# Sheet2.net
KiCad netlist of a schematic drawn in Altium Designer
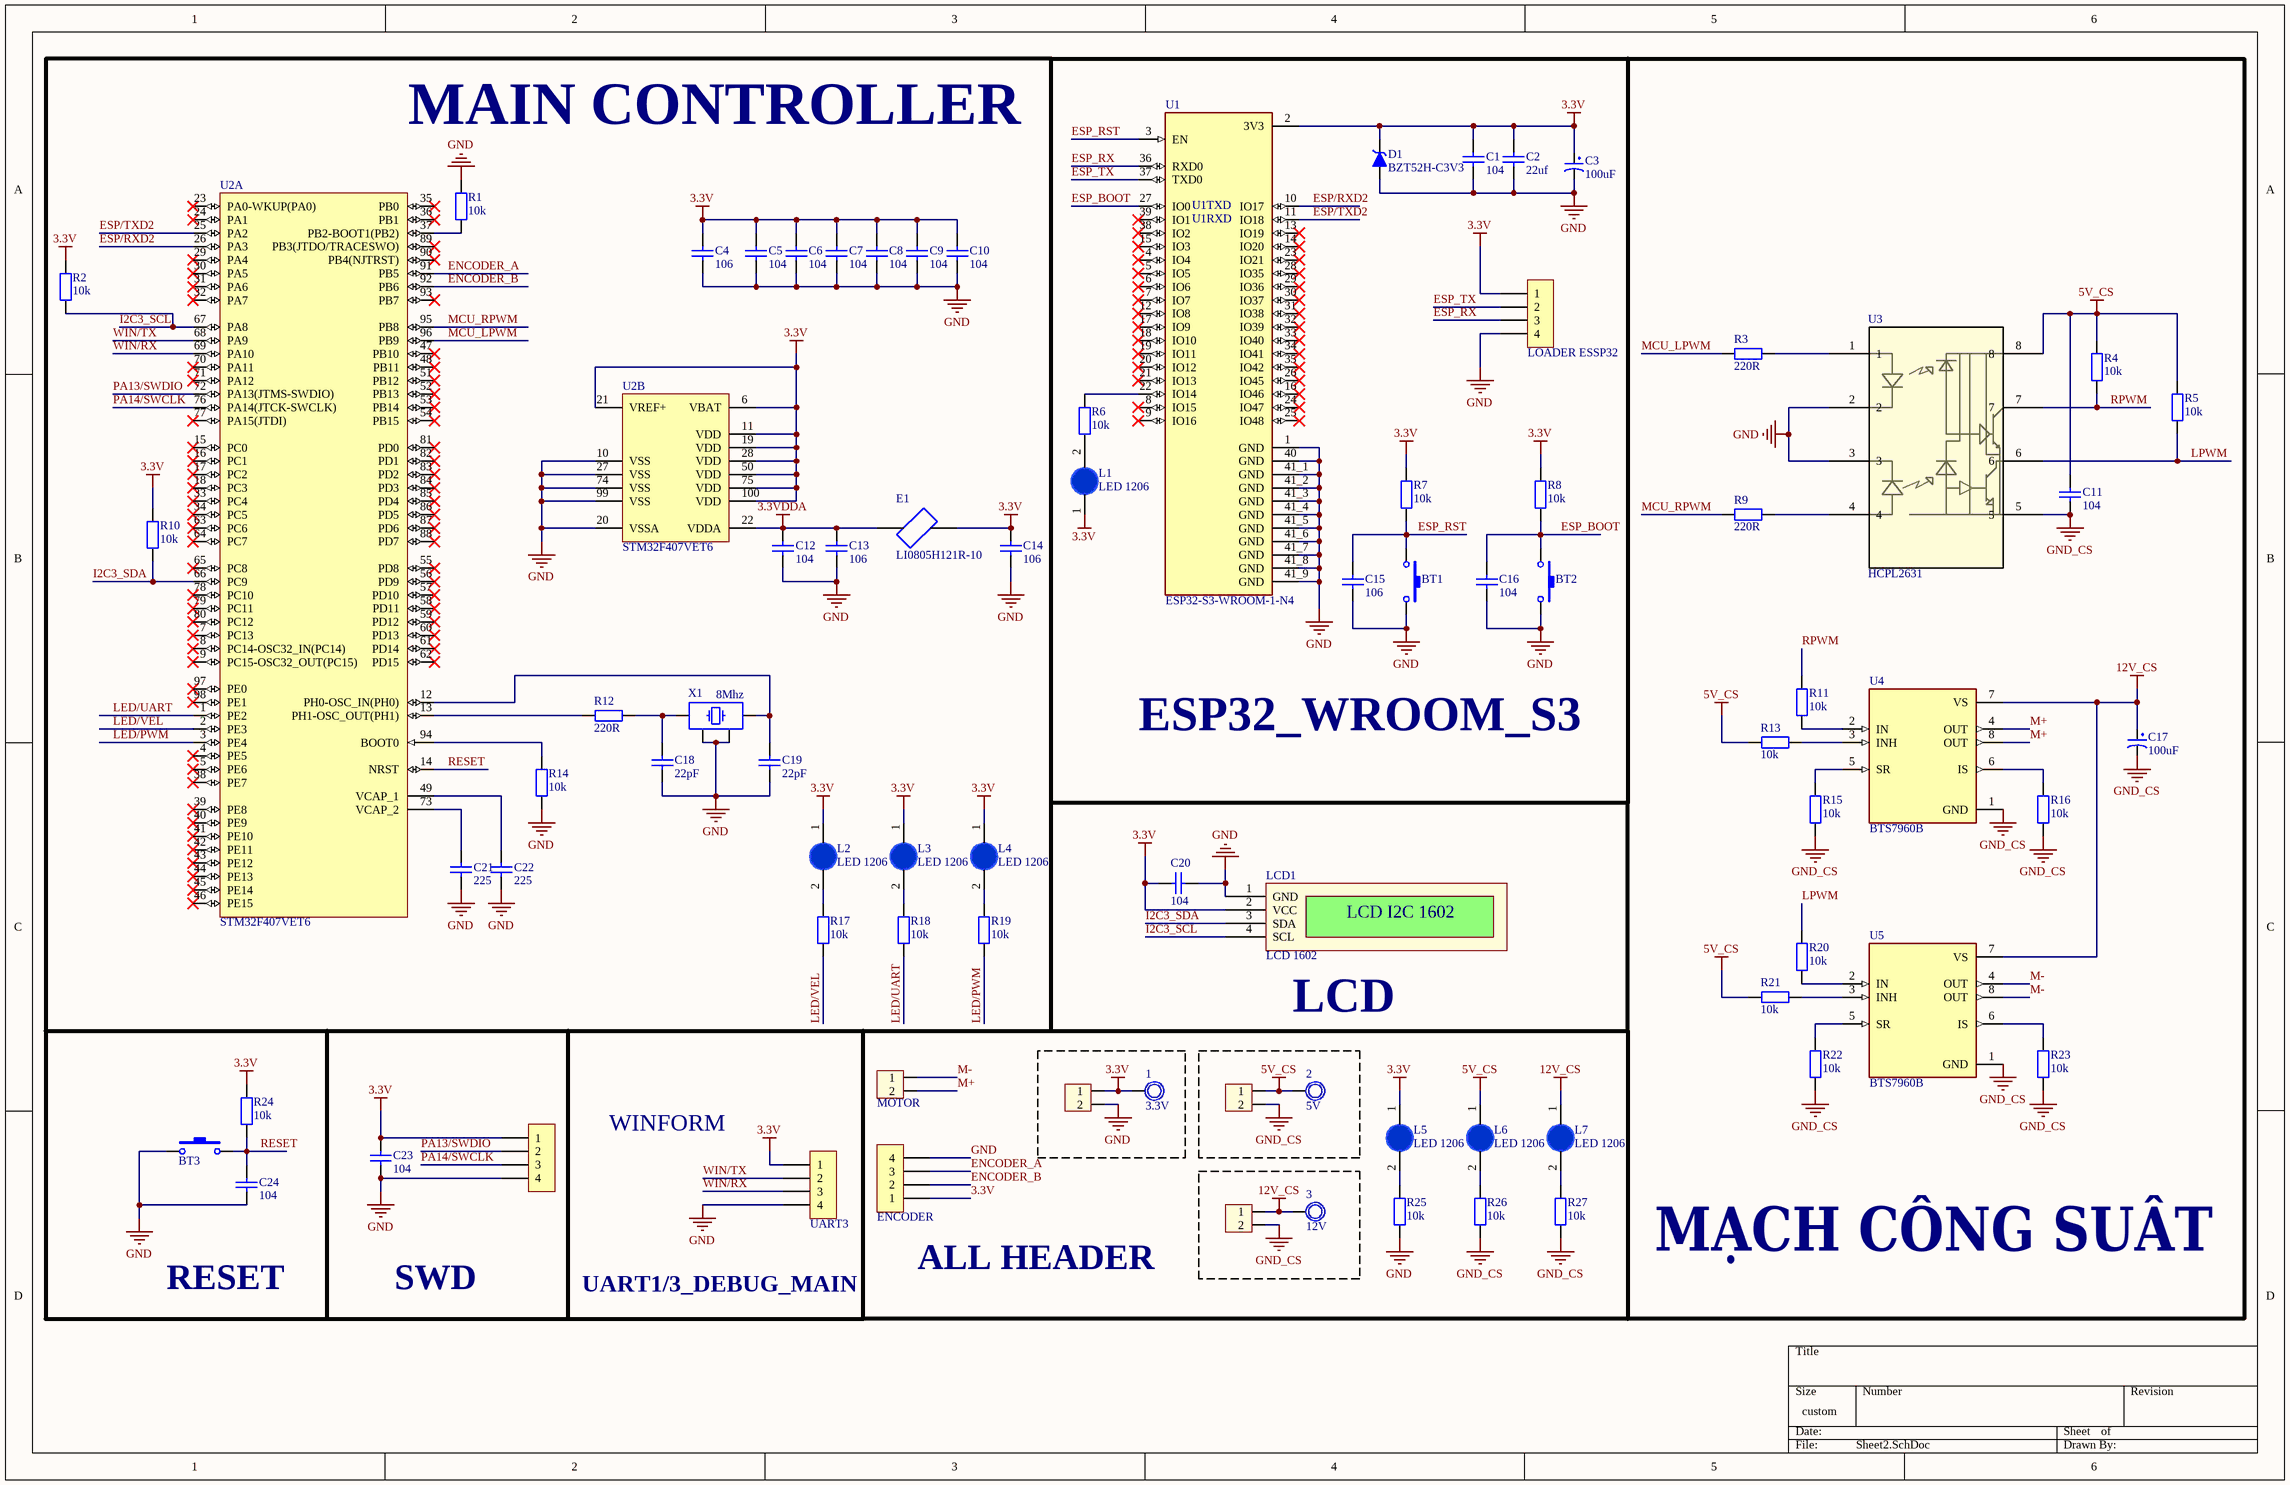
[diagram p0: Sheet2.SchDoc]

(export (version "E")
  (design (tool "Eeschema 10.0.6"))
  (components
    (comp (ref "1")
      (value "3.3V")
      (footprint "TP1")
      (description "Test Point")
      (libsource (lib "syhaunguyen") (part "TP1"))
    )
    (comp (ref "2")
      (value "5V")
      (footprint "TP1")
      (description "Test Point")
      (libsource (lib "syhaunguyen") (part "TP1"))
    )
    (comp (ref "3")
      (value "12V")
      (footprint "TP1")
      (description "Test Point")
      (libsource (lib "syhaunguyen") (part "TP1"))
    )
    (comp (ref "BT1")
      (value "Nut Nhan 2 Chan SMD 3x6x2.5")
      (footprint "Nut Nhan 2 Chan SMD 3x6x2.5")
      (libsource (lib "Altium_Lib_by_KhueNguyenCreator") (part "Nut Nhan 2 Chan SMD 3x6x2.5"))
    )
    (comp (ref "BT2")
      (value "Nut Nhan 2 Chan SMD 3x6x2.5")
      (footprint "Nut Nhan 2 Chan SMD 3x6x2.5")
      (libsource (lib "Altium_Lib_by_KhueNguyenCreator") (part "Nut Nhan 2 Chan SMD 3x6x2.5"))
    )
    (comp (ref "BT3")
      (value "Nut Nhan 2 Chan SMD 3x6x2.5")
      (footprint "Nut Nhan 2 Chan SMD 3x6x2.5")
      (libsource (lib "Altium_Lib_by_KhueNguyenCreator") (part "Nut Nhan 2 Chan SMD 3x6x2.5"))
    )
    (comp (ref "C1")
      (value "104")
      (footprint "tu 0805")
      (description "Dán")
      (libsource (lib "Altium_Lib_by_KhueNguyenCreator") (part "Tu 0805 104 50V 10%"))
    )
    (comp (ref "C2")
      (value "22uf")
      (footprint "tu 0805")
      (description "Dán")
      (libsource (lib "Altium_Lib_by_KhueNguyenCreator") (part "Tu 0805 222 50V 10%"))
    )
    (comp (ref "C3")
      (value "100uF")
      (footprint "tu tantalum smd7343")
      (description "Dán")
      (libsource (lib "Altium_Lib_by_KhueNguyenCreator") (part "Tu tantalum 100uF 50V SMD7343"))
    )
    (comp (ref "C4")
      (value "106")
      (footprint "tu 0805")
      (description "Dán")
      (libsource (lib "Altium_Lib_by_KhueNguyenCreator") (part "Tu 0805 106 16V 10%"))
    )
    (comp (ref "C5")
      (value "104")
      (footprint "tu 0805")
      (description "Dán")
      (libsource (lib "Altium_Lib_by_KhueNguyenCreator") (part "Tu 0805 104 50V 10%"))
    )
    (comp (ref "C6")
      (value "104")
      (footprint "tu 0805")
      (description "Dán")
      (libsource (lib "Altium_Lib_by_KhueNguyenCreator") (part "Tu 0805 104 50V 10%"))
    )
    (comp (ref "C7")
      (value "104")
      (footprint "tu 0805")
      (description "Dán")
      (libsource (lib "Altium_Lib_by_KhueNguyenCreator") (part "Tu 0805 104 50V 10%"))
    )
    (comp (ref "C8")
      (value "104")
      (footprint "tu 0805")
      (description "Dán")
      (libsource (lib "Altium_Lib_by_KhueNguyenCreator") (part "Tu 0805 104 50V 10%"))
    )
    (comp (ref "C9")
      (value "104")
      (footprint "tu 0805")
      (description "Dán")
      (libsource (lib "Altium_Lib_by_KhueNguyenCreator") (part "Tu 0805 104 50V 10%"))
    )
    (comp (ref "C10")
      (value "104")
      (footprint "tu 0805")
      (description "Dán")
      (libsource (lib "Altium_Lib_by_KhueNguyenCreator") (part "Tu 0805 104 50V 10%"))
    )
    (comp (ref "C11")
      (value "104")
      (footprint "tu 0805")
      (description "Dán")
      (libsource (lib "Altium_Lib_by_KhueNguyenCreator") (part "Tu 0805 104 50V 10%"))
    )
    (comp (ref "C12")
      (value "104")
      (footprint "tu 0805")
      (description "Dán")
      (libsource (lib "Altium_Lib_by_KhueNguyenCreator") (part "Tu 0805 104 50V 10%"))
    )
    (comp (ref "C13")
      (value "106")
      (footprint "tu 0805")
      (description "Dán")
      (libsource (lib "Altium_Lib_by_KhueNguyenCreator") (part "Tu 0805 106 16V 10%"))
    )
    (comp (ref "C14")
      (value "106")
      (footprint "tu 0805")
      (description "Dán")
      (libsource (lib "Altium_Lib_by_KhueNguyenCreator") (part "Tu 0805 106 16V 10%"))
    )
    (comp (ref "C15")
      (value "106")
      (footprint "tu 0805")
      (description "Dán")
      (libsource (lib "Altium_Lib_by_KhueNguyenCreator") (part "Tu 0805 106 16V 10%"))
    )
    (comp (ref "C16")
      (value "104")
      (footprint "tu 0805")
      (description "Dán")
      (libsource (lib "Altium_Lib_by_KhueNguyenCreator") (part "Tu 0805 104 50V 10%"))
    )
    (comp (ref "C17")
      (value "100uF")
      (footprint "tu hoa 8mm")
      (description "Cắm")
      (libsource (lib "Altium_Lib_by_KhueNguyenCreator") (part "Tu Hoa 100uF 35V 8x11"))
    )
    (comp (ref "C18")
      (value "22pF")
      (footprint "tu 0805")
      (description "Dán")
      (libsource (lib "Altium_Lib_by_KhueNguyenCreator") (part "Tu 0805 22pF 50V 10%"))
    )
    (comp (ref "C19")
      (value "22pF")
      (footprint "tu 0805")
      (description "Dán")
      (libsource (lib "Altium_Lib_by_KhueNguyenCreator") (part "Tu 0805 22pF 50V 10%"))
    )
    (comp (ref "C20")
      (value "104")
      (footprint "tu 0805")
      (description "Dán")
      (libsource (lib "Altium_Lib_by_KhueNguyenCreator") (part "Tu 0805 104 50V 10%"))
    )
    (comp (ref "C21")
      (value "225")
      (footprint "tu 0805")
      (description "Dán")
      (libsource (lib "Altium_Lib_by_KhueNguyenCreator") (part "Tu 0805 225 25V 10%"))
    )
    (comp (ref "C22")
      (value "225")
      (footprint "tu 0805")
      (description "Dán")
      (libsource (lib "Altium_Lib_by_KhueNguyenCreator") (part "Tu 0805 225 25V 10%"))
    )
    (comp (ref "C23")
      (value "104")
      (footprint "tu 0805")
      (description "Dán")
      (libsource (lib "Altium_Lib_by_KhueNguyenCreator") (part "Tu 0805 104 50V 10%"))
    )
    (comp (ref "C24")
      (value "104")
      (footprint "tu 0805")
      (description "Dán")
      (libsource (lib "Altium_Lib_by_KhueNguyenCreator") (part "Tu 0805 104 50V 10%"))
    )
    (comp (ref "D1")
      (value "BZT52H-C3V3")
      (footprint "SOD123")
      (description "Zener Diode")
      (libsource (lib "chipfc_libs") (part "Diode Zener"))
    )
    (comp (ref "E1")
      (value "LI0805H121R-10")
      (footprint "FB_LI0805H121R-10")
      (fields (field (name "MF") "Laird"))
      (libsource (lib "LI0805H121R-10") (part "LI0805H121R-10"))
    )
    (comp (ref "H1")
      (value "LOADER ESSP32")
      (footprint "XH2.54M-4")
      (description "Cắm")
      (libsource (lib "") (part "Header 4P 2.54 Duc Thang_1"))
    )
    (comp (ref "H2")
      (value "MOTOR")
      (footprint "XH2.54M-2")
      (description "Cắm")
      (libsource (lib "Altium_Lib_by_KhueNguyenCreator") (part "Header 2P 2.54 Duc Thang"))
    )
    (comp (ref "H3")
      (value "Header 2P 2.54 Duc Thang")
      (footprint "XH2.54M-2")
      (description "Cắm")
      (libsource (lib "Altium_Lib_by_KhueNguyenCreator") (part "Header 2P 2.54 Duc Thang"))
    )
    (comp (ref "H4")
      (value "Header 2P 2.54 Duc Thang")
      (footprint "XH2.54M-2")
      (description "Cắm")
      (libsource (lib "Altium_Lib_by_KhueNguyenCreator") (part "Header 2P 2.54 Duc Thang"))
    )
    (comp (ref "H5")
      (value "Header 4P 2.54 Duc Thang")
      (footprint "XH2.54M-4")
      (description "Cắm")
      (libsource (lib "") (part "Header 4P 2.54 Duc Thang_1"))
    )
    (comp (ref "H6")
      (value "ENCODER")
      (footprint "XH2.54M-4")
      (description "Cắm")
      (libsource (lib "Altium_Lib_by_KhueNguyenCreator") (part "Header 4P 2.54 Duc Thang"))
    )
    (comp (ref "H7")
      (value "UART3")
      (footprint "XH2.54M-4")
      (description "Cắm")
      (libsource (lib "") (part "Header 4P 2.54 Duc Thang_1"))
    )
    (comp (ref "H8")
      (value "Header 2P 2.54 Duc Thang")
      (footprint "XH2.54M-2")
      (description "Cắm")
      (libsource (lib "Altium_Lib_by_KhueNguyenCreator") (part "Header 2P 2.54 Duc Thang"))
    )
    (comp (ref "L1")
      (value "LED 1206")
      (footprint "LED-1206-Blue")
      (description "Dán")
      (libsource (lib "Altium_Lib_by_KhueNguyenCreator") (part "LED 1206 Xanh Duong"))
    )
    (comp (ref "L2")
      (value "LED 1206")
      (footprint "LED-1206-Blue")
      (description "Dán")
      (libsource (lib "Altium_Lib_by_KhueNguyenCreator") (part "LED 1206 Xanh Duong"))
    )
    (comp (ref "L3")
      (value "LED 1206")
      (footprint "LED-1206-Blue")
      (description "Dán")
      (libsource (lib "Altium_Lib_by_KhueNguyenCreator") (part "LED 1206 Xanh Duong"))
    )
    (comp (ref "L4")
      (value "LED 1206")
      (footprint "LED-1206-Blue")
      (description "Dán")
      (libsource (lib "Altium_Lib_by_KhueNguyenCreator") (part "LED 1206 Xanh Duong"))
    )
    (comp (ref "L5")
      (value "LED 1206")
      (footprint "LED-1206-Blue")
      (description "Dán")
      (libsource (lib "Altium_Lib_by_KhueNguyenCreator") (part "LED 1206 Xanh Duong"))
    )
    (comp (ref "L6")
      (value "LED 1206")
      (footprint "LED-1206-Blue")
      (description "Dán")
      (libsource (lib "Altium_Lib_by_KhueNguyenCreator") (part "LED 1206 Xanh Duong"))
    )
    (comp (ref "L7")
      (value "LED 1206")
      (footprint "LED-1206-Blue")
      (description "Dán")
      (libsource (lib "Altium_Lib_by_KhueNguyenCreator") (part "LED 1206 Xanh Duong"))
    )
    (comp (ref "LCD1")
      (value "LCD 1602")
      (footprint "LCD-I2C-1602")
      (libsource (lib "LCD-I2C-1602") (part "LCD 1602"))
    )
    (comp (ref "R1")
      (value "10k")
      (footprint "tro smd 0805")
      (description "Dán")
      (libsource (lib "Altium_Lib_by_KhueNguyenCreator") (part "Tro 0805 1% 10k"))
    )
    (comp (ref "R2")
      (value "10k")
      (footprint "tro smd 0805")
      (description "Dán")
      (libsource (lib "Altium_Lib_by_KhueNguyenCreator") (part "Tro 0805 1% 10k"))
    )
    (comp (ref "R3")
      (value "220R")
      (footprint "tro smd 0805")
      (description "Dán")
      (libsource (lib "Altium_Lib_by_KhueNguyenCreator") (part "Tro 0805 5% 220R"))
    )
    (comp (ref "R4")
      (value "10k")
      (footprint "tro smd 0805")
      (description "Dán")
      (libsource (lib "Altium_Lib_by_KhueNguyenCreator") (part "Tro 0805 5% 10k"))
    )
    (comp (ref "R5")
      (value "10k")
      (footprint "tro smd 0805")
      (description "Dán")
      (libsource (lib "Altium_Lib_by_KhueNguyenCreator") (part "Tro 0805 5% 10k"))
    )
    (comp (ref "R6")
      (value "10k")
      (footprint "tro smd 0805")
      (description "Dán")
      (libsource (lib "Altium_Lib_by_KhueNguyenCreator") (part "Tro 0805 1% 10k"))
    )
    (comp (ref "R7")
      (value "10k")
      (footprint "tro smd 0805")
      (description "Dán")
      (libsource (lib "Altium_Lib_by_KhueNguyenCreator") (part "Tro 0805 5% 10k"))
    )
    (comp (ref "R8")
      (value "10k")
      (footprint "tro smd 0805")
      (description "Dán")
      (libsource (lib "Altium_Lib_by_KhueNguyenCreator") (part "Tro 0805 5% 10k"))
    )
    (comp (ref "R9")
      (value "220R")
      (footprint "tro smd 0805")
      (description "Dán")
      (libsource (lib "Altium_Lib_by_KhueNguyenCreator") (part "Tro 0805 5% 220R"))
    )
    (comp (ref "R10")
      (value "10k")
      (footprint "tro smd 0805")
      (description "Dán")
      (libsource (lib "Altium_Lib_by_KhueNguyenCreator") (part "Tro 0805 1% 10k"))
    )
    (comp (ref "R11")
      (value "10k")
      (footprint "tro smd 0805")
      (description "Dán")
      (libsource (lib "Altium_Lib_by_KhueNguyenCreator") (part "Tro 0805 5% 10k"))
    )
    (comp (ref "R12")
      (value "220R")
      (footprint "tro smd 0805")
      (description "Dán")
      (libsource (lib "Altium_Lib_by_KhueNguyenCreator") (part "Tro 0805 5% 220R"))
    )
    (comp (ref "R13")
      (value "10k")
      (footprint "tro smd 0805")
      (description "Dán")
      (libsource (lib "Altium_Lib_by_KhueNguyenCreator") (part "Tro 0805 5% 10k"))
    )
    (comp (ref "R14")
      (value "10k")
      (footprint "tro smd 0805")
      (description "Dán")
      (libsource (lib "Altium_Lib_by_KhueNguyenCreator") (part "Tro 0805 1% 10k"))
    )
    (comp (ref "R15")
      (value "10k")
      (footprint "tro smd 0805")
      (description "Dán")
      (libsource (lib "Altium_Lib_by_KhueNguyenCreator") (part "Tro 0805 5% 10k"))
    )
    (comp (ref "R16")
      (value "10k")
      (footprint "tro smd 0805")
      (description "Dán")
      (libsource (lib "Altium_Lib_by_KhueNguyenCreator") (part "Tro 0805 5% 10k"))
    )
    (comp (ref "R17")
      (value "10k")
      (footprint "tro smd 0805")
      (description "Dán")
      (libsource (lib "Altium_Lib_by_KhueNguyenCreator") (part "Tro 0805 1% 10k"))
    )
    (comp (ref "R18")
      (value "10k")
      (footprint "tro smd 0805")
      (description "Dán")
      (libsource (lib "Altium_Lib_by_KhueNguyenCreator") (part "Tro 0805 1% 10k"))
    )
    (comp (ref "R19")
      (value "10k")
      (footprint "tro smd 0805")
      (description "Dán")
      (libsource (lib "Altium_Lib_by_KhueNguyenCreator") (part "Tro 0805 1% 10k"))
    )
    (comp (ref "R20")
      (value "10k")
      (footprint "tro smd 0805")
      (description "Dán")
      (libsource (lib "Altium_Lib_by_KhueNguyenCreator") (part "Tro 0805 5% 10k"))
    )
    (comp (ref "R21")
      (value "10k")
      (footprint "tro smd 0805")
      (description "Dán")
      (libsource (lib "Altium_Lib_by_KhueNguyenCreator") (part "Tro 0805 5% 10k"))
    )
    (comp (ref "R22")
      (value "10k")
      (footprint "tro smd 0805")
      (description "Dán")
      (libsource (lib "Altium_Lib_by_KhueNguyenCreator") (part "Tro 0805 5% 10k"))
    )
    (comp (ref "R23")
      (value "10k")
      (footprint "tro smd 0805")
      (description "Dán")
      (libsource (lib "Altium_Lib_by_KhueNguyenCreator") (part "Tro 0805 5% 10k"))
    )
    (comp (ref "R24")
      (value "10k")
      (footprint "tro smd 0805")
      (description "Dán")
      (libsource (lib "Altium_Lib_by_KhueNguyenCreator") (part "Tro 0805 1% 10k"))
    )
    (comp (ref "R25")
      (value "10k")
      (footprint "tro smd 0805")
      (description "Dán")
      (libsource (lib "Altium_Lib_by_KhueNguyenCreator") (part "Tro 0805 1% 10k"))
    )
    (comp (ref "R26")
      (value "10k")
      (footprint "tro smd 0805")
      (description "Dán")
      (libsource (lib "Altium_Lib_by_KhueNguyenCreator") (part "Tro 0805 1% 10k"))
    )
    (comp (ref "R27")
      (value "10k")
      (footprint "tro smd 0805")
      (description "Dán")
      (libsource (lib "Altium_Lib_by_KhueNguyenCreator") (part "Tro 0805 1% 10k"))
    )
    (comp (ref "U1")
      (value "ESP32-S3-WROOM-1-N4")
      (footprint "XCVR_ESP32-S3-WROOM-1-N4")
      (fields (field (name "MF") "{'manufacturer': u'Espressif Systems'}"))
      (libsource (lib "ESP32-S3-WROOM-1-N4") (part "ESP32-S3-WROOM-1-N4"))
    )
    (comp (ref "U2")
      (value "STM32F407VET6")
      (footprint "STM-LQFP100_N")
      (fields (field (name "MANUFACTURER") "STMicroelectronics"))
      (libsource (lib "Altium Content Vault") (part "MC-ARM-STM32F40X_41X-SQ100"))
    )
    (comp (ref "U3")
      (value "HCPL2631")
      (footprint "DIP_PL2631_ONS")
      (description "Description")
      (fields (field (name "COPYRIGHT") "Copyright (C) 2025 Ultra Librarian. All rights reserved."))
      (libsource (lib "HCPL2631") (part "HCPL2631"))
    )
    (comp (ref "U4")
      (value "BTS7960B")
      (footprint "DPAK127P1490X440-8N")
      (description "Half Bridge Driver DC Motors, General Purpose DMOS PG-TO263-7-1")
      (fields (field (name "MF") "Infineon"))
      (libsource (lib "BTS7960B") (part "BTS7960B"))
    )
    (comp (ref "U5")
      (value "BTS7960B")
      (footprint "DPAK127P1490X440-8N")
      (description "Half Bridge Driver DC Motors, General Purpose DMOS PG-TO263-7-1")
      (fields (field (name "MF") "Infineon"))
      (libsource (lib "BTS7960B") (part "BTS7960B"))
    )
    (comp (ref "X1")
      (value "8Mhz")
      (footprint "XTAL_3225")
      (description "Crystal SMD 24MHz 10PPM 7pF 3225")
      (fields
        (field (name "MANUFACTURER") "Epson")
        (field (name "MANUFACTURER PART NUMBER") "TSX-3225 24.0000MF15X-AC")
      )
      (libsource (lib "Schematic-Lib-PhilsLab") (part "TSX-3225_24.0000MF15X-AC"))
    )
  )
  (nets
    (net (code "1") (name "/ENCODER_A") (class "Default")
      (node (ref "H6") (pin "3") (pinfunction "3_3") (pintype "passive"))
      (node (ref "U2") (pin "91") (pinfunction "PB5_91") (pintype "bidirectional"))
    )
    (net (code "2") (name "/ENCODER_B") (class "Default")
      (node (ref "H6") (pin "2") (pinfunction "2_2") (pintype "passive"))
      (node (ref "U2") (pin "92") (pinfunction "PB6_92") (pintype "bidirectional"))
    )
    (net (code "3") (name "/ESP_BOOT") (class "Default")
      (node (ref "BT2") (pin "1") (pinfunction "1_1") (pintype "passive"))
      (node (ref "C16") (pin "1") (pinfunction "1_1") (pintype "passive"))
      (node (ref "R8") (pin "1") (pinfunction "1_1") (pintype "passive"))
      (node (ref "U1") (pin "27") (pinfunction "IO0_27") (pintype "bidirectional"))
    )
    (net (code "4") (name "/ESP_RST") (class "Default")
      (node (ref "BT1") (pin "1") (pinfunction "1_1") (pintype "passive"))
      (node (ref "C15") (pin "1") (pinfunction "1_1") (pintype "passive"))
      (node (ref "R7") (pin "1") (pinfunction "1_1") (pintype "passive"))
      (node (ref "U1") (pin "3") (pinfunction "EN_3") (pintype "input"))
    )
    (net (code "5") (name "/ESP_RX") (class "Default")
      (node (ref "H1") (pin "3") (pinfunction "3_3") (pintype "passive"))
      (node (ref "U1") (pin "36") (pinfunction "RXD0_36") (pintype "bidirectional"))
    )
    (net (code "6") (name "/ESP_TX") (class "Default")
      (node (ref "H1") (pin "2") (pinfunction "2_2") (pintype "passive"))
      (node (ref "U1") (pin "37") (pinfunction "TXD0_37") (pintype "bidirectional"))
    )
    (net (code "7") (name "/ESP{slash}RXD2") (class "Default")
      (node (ref "U1") (pin "10") (pinfunction "IO17_10") (pintype "bidirectional"))
      (node (ref "U2") (pin "26") (pinfunction "PA3_26") (pintype "bidirectional"))
    )
    (net (code "8") (name "/ESP{slash}TXD2") (class "Default")
      (node (ref "U1") (pin "11") (pinfunction "IO18_11") (pintype "bidirectional"))
      (node (ref "U2") (pin "25") (pinfunction "PA2_25") (pintype "bidirectional"))
    )
    (net (code "9") (name "/I2C3_SCL") (class "Default")
      (node (ref "LCD1") (pin "4") (pinfunction "SCL_4") (pintype "passive"))
      (node (ref "R2") (pin "2") (pinfunction "2_2") (pintype "passive"))
      (node (ref "U2") (pin "67") (pinfunction "PA8_67") (pintype "bidirectional"))
    )
    (net (code "10") (name "/I2C3_SDA") (class "Default")
      (node (ref "LCD1") (pin "3") (pinfunction "SDA_3") (pintype "passive"))
      (node (ref "R10") (pin "1") (pinfunction "1_1") (pintype "passive"))
      (node (ref "U2") (pin "66") (pinfunction "PC9_66") (pintype "bidirectional"))
    )
    (net (code "11") (name "/LED{slash}PWM") (class "Default")
      (node (ref "R19") (pin "1") (pinfunction "1_1") (pintype "passive"))
      (node (ref "U2") (pin "3") (pinfunction "PE4_3") (pintype "bidirectional"))
    )
    (net (code "12") (name "/LED{slash}UART") (class "Default")
      (node (ref "R18") (pin "1") (pinfunction "1_1") (pintype "passive"))
      (node (ref "U2") (pin "1") (pinfunction "PE2_1") (pintype "bidirectional"))
    )
    (net (code "13") (name "/LED{slash}VEL") (class "Default")
      (node (ref "R17") (pin "1") (pinfunction "1_1") (pintype "passive"))
      (node (ref "U2") (pin "2") (pinfunction "PE3_2") (pintype "bidirectional"))
    )
    (net (code "14") (name "/LPWM") (class "Default")
      (node (ref "R20") (pin "2") (pinfunction "2_2") (pintype "passive"))
      (node (ref "R5") (pin "1") (pinfunction "1_1") (pintype "passive"))
      (node (ref "U3") (pin "6") (pinfunction "6_6") (pintype "passive"))
    )
    (net (code "15") (name "/M+") (class "Default")
      (node (ref "H2") (pin "2") (pinfunction "2_2") (pintype "passive"))
      (node (ref "U4") (pin "4") (pinfunction "OUT_4") (pintype "output"))
      (node (ref "U4") (pin "8") (pinfunction "OUT_8") (pintype "output"))
    )
    (net (code "16") (name "/M-") (class "Default")
      (node (ref "H2") (pin "1") (pinfunction "1_1") (pintype "passive"))
      (node (ref "U5") (pin "4") (pinfunction "OUT_4") (pintype "output"))
      (node (ref "U5") (pin "8") (pinfunction "OUT_8") (pintype "output"))
    )
    (net (code "17") (name "/MCU_LPWM") (class "Default")
      (node (ref "R3") (pin "1") (pinfunction "1_1") (pintype "passive"))
      (node (ref "U2") (pin "96") (pinfunction "PB9_96") (pintype "bidirectional"))
    )
    (net (code "18") (name "/MCU_RPWM") (class "Default")
      (node (ref "R9") (pin "1") (pinfunction "1_1") (pintype "passive"))
      (node (ref "U2") (pin "95") (pinfunction "PB8_95") (pintype "bidirectional"))
    )
    (net (code "19") (name "/PA13{slash}SWDIO") (class "Default")
      (node (ref "H5") (pin "2") (pinfunction "2_2") (pintype "passive"))
      (node (ref "U2") (pin "72") (pinfunction "PA13(JTMS-SWDIO)_72") (pintype "bidirectional"))
    )
    (net (code "20") (name "/PA14{slash}SWCLK") (class "Default")
      (node (ref "H5") (pin "3") (pinfunction "3_3") (pintype "passive"))
      (node (ref "U2") (pin "76") (pinfunction "PA14(JTCK-SWCLK)_76") (pintype "bidirectional"))
    )
    (net (code "21") (name "/RESET") (class "Default")
      (node (ref "BT3") (pin "2") (pinfunction "2_2") (pintype "passive"))
      (node (ref "C24") (pin "1") (pinfunction "1_1") (pintype "passive"))
      (node (ref "R24") (pin "1") (pinfunction "1_1") (pintype "passive"))
      (node (ref "U2") (pin "14") (pinfunction "NRST_14") (pintype "bidirectional"))
    )
    (net (code "22") (name "/RPWM") (class "Default")
      (node (ref "R11") (pin "2") (pinfunction "2_2") (pintype "passive"))
      (node (ref "R4") (pin "1") (pinfunction "1_1") (pintype "passive"))
      (node (ref "U3") (pin "7") (pinfunction "7_7") (pintype "passive"))
    )
    (net (code "23") (name "/WIN{slash}RX") (class "Default")
      (node (ref "H7") (pin "3") (pinfunction "3_3") (pintype "passive"))
      (node (ref "U2") (pin "69") (pinfunction "PA10_69") (pintype "bidirectional"))
    )
    (net (code "24") (name "/WIN{slash}TX") (class "Default")
      (node (ref "H7") (pin "2") (pinfunction "2_2") (pintype "passive"))
      (node (ref "U2") (pin "68") (pinfunction "PA9_68") (pintype "bidirectional"))
    )
    (net (code "25") (name "3.3V") (class "Default")
      (node (ref "1") (pin "1") (pinfunction "1_1") (pintype "passive"))
      (node (ref "C1") (pin "1") (pinfunction "1_1") (pintype "passive"))
      (node (ref "C10") (pin "1") (pinfunction "1_1") (pintype "passive"))
      (node (ref "C14") (pin "1") (pinfunction "1_1") (pintype "passive"))
      (node (ref "C2") (pin "2") (pinfunction "2_2") (pintype "passive"))
      (node (ref "C20") (pin "1") (pinfunction "1_1") (pintype "passive"))
      (node (ref "C23") (pin "1") (pinfunction "1_1") (pintype "passive"))
      (node (ref "C3") (pin "1") (pinfunction "1_1") (pintype "passive"))
      (node (ref "C4") (pin "1") (pinfunction "1_1") (pintype "passive"))
      (node (ref "C5") (pin "1") (pinfunction "1_1") (pintype "passive"))
      (node (ref "C6") (pin "1") (pinfunction "1_1") (pintype "passive"))
      (node (ref "C7") (pin "1") (pinfunction "1_1") (pintype "passive"))
      (node (ref "C8") (pin "1") (pinfunction "1_1") (pintype "passive"))
      (node (ref "C9") (pin "1") (pinfunction "1_1") (pintype "passive"))
      (node (ref "D1") (pin "2") (pinfunction "K_2") (pintype "passive"))
      (node (ref "E1") (pin "2") (pinfunction "2_2") (pintype "passive"))
      (node (ref "H1") (pin "1") (pinfunction "1_1") (pintype "passive"))
      (node (ref "H3") (pin "1") (pinfunction "1_1") (pintype "passive"))
      (node (ref "H5") (pin "1") (pinfunction "1_1") (pintype "passive"))
      (node (ref "H6") (pin "1") (pinfunction "1_1") (pintype "passive"))
      (node (ref "H7") (pin "1") (pinfunction "1_1") (pintype "passive"))
      (node (ref "L1") (pin "1") (pinfunction "A_1") (pintype "passive"))
      (node (ref "L2") (pin "1") (pinfunction "A_1") (pintype "passive"))
      (node (ref "L3") (pin "1") (pinfunction "A_1") (pintype "passive"))
      (node (ref "L4") (pin "1") (pinfunction "A_1") (pintype "passive"))
      (node (ref "L5") (pin "1") (pinfunction "A_1") (pintype "passive"))
      (node (ref "LCD1") (pin "2") (pinfunction "VCC_2") (pintype "passive"))
      (node (ref "R10") (pin "2") (pinfunction "2_2") (pintype "passive"))
      (node (ref "R2") (pin "1") (pinfunction "1_1") (pintype "passive"))
      (node (ref "R24") (pin "2") (pinfunction "2_2") (pintype "passive"))
      (node (ref "R7") (pin "2") (pinfunction "2_2") (pintype "passive"))
      (node (ref "R8") (pin "2") (pinfunction "2_2") (pintype "passive"))
      (node (ref "U1") (pin "2") (pinfunction "3V3_2") (pintype "power_in"))
      (node (ref "U2") (pin "100") (pinfunction "VDD_100") (pintype "power_in"))
      (node (ref "U2") (pin "11") (pinfunction "VDD_11") (pintype "power_in"))
      (node (ref "U2") (pin "19") (pinfunction "VDD_19") (pintype "power_in"))
      (node (ref "U2") (pin "21") (pinfunction "VREF+_21") (pintype "power_in"))
      (node (ref "U2") (pin "28") (pinfunction "VDD_28") (pintype "power_in"))
      (node (ref "U2") (pin "50") (pinfunction "VDD_50") (pintype "power_in"))
      (node (ref "U2") (pin "6") (pinfunction "VBAT_6") (pintype "power_in"))
      (node (ref "U2") (pin "75") (pinfunction "VDD_75") (pintype "power_in"))
    )
    (net (code "26") (name "3.3VDDA") (class "Default")
      (node (ref "C12") (pin "1") (pinfunction "1_1") (pintype "passive"))
      (node (ref "C13") (pin "1") (pinfunction "1_1") (pintype "passive"))
      (node (ref "E1") (pin "1") (pinfunction "1_1") (pintype "passive"))
      (node (ref "U2") (pin "22") (pinfunction "VDDA_22") (pintype "power_in"))
    )
    (net (code "27") (name "5V_CS") (class "Default")
      (node (ref "2") (pin "1") (pinfunction "1_1") (pintype "passive"))
      (node (ref "C11") (pin "1") (pinfunction "1_1") (pintype "passive"))
      (node (ref "H4") (pin "1") (pinfunction "1_1") (pintype "passive"))
      (node (ref "L6") (pin "1") (pinfunction "A_1") (pintype "passive"))
      (node (ref "R13") (pin "2") (pinfunction "2_2") (pintype "passive"))
      (node (ref "R21") (pin "2") (pinfunction "2_2") (pintype "passive"))
      (node (ref "R4") (pin "2") (pinfunction "2_2") (pintype "passive"))
      (node (ref "R5") (pin "2") (pinfunction "2_2") (pintype "passive"))
      (node (ref "U3") (pin "8") (pinfunction "8_8") (pintype "passive"))
    )
    (net (code "28") (name "12V_CS") (class "Default")
      (node (ref "3") (pin "1") (pinfunction "1_1") (pintype "passive"))
      (node (ref "C17") (pin "1") (pinfunction "1_1") (pintype "passive"))
      (node (ref "H8") (pin "1") (pinfunction "1_1") (pintype "passive"))
      (node (ref "L7") (pin "1") (pinfunction "A_1") (pintype "passive"))
      (node (ref "U4") (pin "7") (pinfunction "VS_7") (pintype "power_in"))
      (node (ref "U5") (pin "7") (pinfunction "VS_7") (pintype "power_in"))
    )
    (net (code "29") (name "GND") (class "Default")
      (node (ref "BT1") (pin "2") (pinfunction "2_2") (pintype "passive"))
      (node (ref "BT2") (pin "2") (pinfunction "2_2") (pintype "passive"))
      (node (ref "BT3") (pin "1") (pinfunction "1_1") (pintype "passive"))
      (node (ref "C1") (pin "2") (pinfunction "2_2") (pintype "passive"))
      (node (ref "C10") (pin "2") (pinfunction "2_2") (pintype "passive"))
      (node (ref "C12") (pin "2") (pinfunction "2_2") (pintype "passive"))
      (node (ref "C13") (pin "2") (pinfunction "2_2") (pintype "passive"))
      (node (ref "C14") (pin "2") (pinfunction "2_2") (pintype "passive"))
      (node (ref "C15") (pin "2") (pinfunction "2_2") (pintype "passive"))
      (node (ref "C16") (pin "2") (pinfunction "2_2") (pintype "passive"))
      (node (ref "C18") (pin "2") (pinfunction "2_2") (pintype "passive"))
      (node (ref "C19") (pin "2") (pinfunction "2_2") (pintype "passive"))
      (node (ref "C2") (pin "1") (pinfunction "1_1") (pintype "passive"))
      (node (ref "C20") (pin "2") (pinfunction "2_2") (pintype "passive"))
      (node (ref "C21") (pin "2") (pinfunction "2_2") (pintype "passive"))
      (node (ref "C22") (pin "2") (pinfunction "2_2") (pintype "passive"))
      (node (ref "C23") (pin "2") (pinfunction "2_2") (pintype "passive"))
      (node (ref "C24") (pin "2") (pinfunction "2_2") (pintype "passive"))
      (node (ref "C3") (pin "2") (pinfunction "2_2") (pintype "passive"))
      (node (ref "C4") (pin "2") (pinfunction "2_2") (pintype "passive"))
      (node (ref "C5") (pin "2") (pinfunction "2_2") (pintype "passive"))
      (node (ref "C6") (pin "2") (pinfunction "2_2") (pintype "passive"))
      (node (ref "C7") (pin "2") (pinfunction "2_2") (pintype "passive"))
      (node (ref "C8") (pin "2") (pinfunction "2_2") (pintype "passive"))
      (node (ref "C9") (pin "2") (pinfunction "2_2") (pintype "passive"))
      (node (ref "D1") (pin "1") (pinfunction "A_1") (pintype "passive"))
      (node (ref "H1") (pin "4") (pinfunction "4_4") (pintype "passive"))
      (node (ref "H3") (pin "2") (pinfunction "2_2") (pintype "passive"))
      (node (ref "H5") (pin "4") (pinfunction "4_4") (pintype "passive"))
      (node (ref "H6") (pin "4") (pinfunction "4_4") (pintype "passive"))
      (node (ref "H7") (pin "4") (pinfunction "4_4") (pintype "passive"))
      (node (ref "LCD1") (pin "1") (pinfunction "GND_1") (pintype "passive"))
      (node (ref "R1") (pin "1") (pinfunction "1_1") (pintype "passive"))
      (node (ref "R14") (pin "1") (pinfunction "1_1") (pintype "passive"))
      (node (ref "R25") (pin "1") (pinfunction "1_1") (pintype "passive"))
      (node (ref "U1") (pin "1") (pinfunction "GND_1") (pintype "power_in"))
      (node (ref "U1") (pin "40") (pinfunction "GND_40") (pintype "power_in"))
      (node (ref "U1") (pin "41_1") (pinfunction "GND_41_1") (pintype "power_in"))
      (node (ref "U1") (pin "41_2") (pinfunction "GND_41_2") (pintype "power_in"))
      (node (ref "U1") (pin "41_3") (pinfunction "GND_41_3") (pintype "power_in"))
      (node (ref "U1") (pin "41_4") (pinfunction "GND_41_4") (pintype "power_in"))
      (node (ref "U1") (pin "41_5") (pinfunction "GND_41_5") (pintype "power_in"))
      (node (ref "U1") (pin "41_6") (pinfunction "GND_41_6") (pintype "power_in"))
      (node (ref "U1") (pin "41_7") (pinfunction "GND_41_7") (pintype "power_in"))
      (node (ref "U1") (pin "41_8") (pinfunction "GND_41_8") (pintype "power_in"))
      (node (ref "U1") (pin "41_9") (pinfunction "GND_41_9") (pintype "power_in"))
      (node (ref "U2") (pin "10") (pinfunction "VSS_10") (pintype "power_in"))
      (node (ref "U2") (pin "20") (pinfunction "VSSA_20") (pintype "power_in"))
      (node (ref "U2") (pin "27") (pinfunction "VSS_27") (pintype "power_in"))
      (node (ref "U2") (pin "74") (pinfunction "VSS_74") (pintype "power_in"))
      (node (ref "U2") (pin "99") (pinfunction "VSS_99") (pintype "power_in"))
      (node (ref "U3") (pin "2") (pinfunction "2_2") (pintype "passive"))
      (node (ref "U3") (pin "3") (pinfunction "3_3") (pintype "passive"))
      (node (ref "X1") (pin "2") (pinfunction "2_2") (pintype "passive"))
      (node (ref "X1") (pin "4") (pinfunction "4_4") (pintype "passive"))
    )
    (net (code "30") (name "GND_CS") (class "Default")
      (node (ref "C11") (pin "2") (pinfunction "2_2") (pintype "passive"))
      (node (ref "C17") (pin "2") (pinfunction "2_2") (pintype "passive"))
      (node (ref "H4") (pin "2") (pinfunction "2_2") (pintype "passive"))
      (node (ref "H8") (pin "2") (pinfunction "2_2") (pintype "passive"))
      (node (ref "R15") (pin "2") (pinfunction "2_2") (pintype "passive"))
      (node (ref "R16") (pin "2") (pinfunction "2_2") (pintype "passive"))
      (node (ref "R22") (pin "2") (pinfunction "2_2") (pintype "passive"))
      (node (ref "R23") (pin "2") (pinfunction "2_2") (pintype "passive"))
      (node (ref "R26") (pin "1") (pinfunction "1_1") (pintype "passive"))
      (node (ref "R27") (pin "1") (pinfunction "1_1") (pintype "passive"))
      (node (ref "U3") (pin "5") (pinfunction "5_5") (pintype "passive"))
      (node (ref "U4") (pin "1") (pinfunction "GND_1") (pintype "power_in"))
      (node (ref "U5") (pin "1") (pinfunction "GND_1") (pintype "power_in"))
    )
    (net (code "31") (name "Net-(C18-Pad1)") (class "Default")
      (node (ref "C18") (pin "1") (pinfunction "1_1") (pintype "passive"))
      (node (ref "R12") (pin "2") (pinfunction "2_2") (pintype "passive"))
      (node (ref "X1") (pin "1") (pinfunction "1_1") (pintype "passive"))
    )
    (net (code "32") (name "Net-(L1-K)") (class "Default")
      (node (ref "L1") (pin "2") (pinfunction "K_2") (pintype "passive"))
      (node (ref "R6") (pin "2") (pinfunction "2_2") (pintype "passive"))
    )
    (net (code "33") (name "Net-(L2-K)") (class "Default")
      (node (ref "L2") (pin "2") (pinfunction "K_2") (pintype "passive"))
      (node (ref "R17") (pin "2") (pinfunction "2_2") (pintype "passive"))
    )
    (net (code "34") (name "Net-(L3-K)") (class "Default")
      (node (ref "L3") (pin "2") (pinfunction "K_2") (pintype "passive"))
      (node (ref "R18") (pin "2") (pinfunction "2_2") (pintype "passive"))
    )
    (net (code "35") (name "Net-(L4-K)") (class "Default")
      (node (ref "L4") (pin "2") (pinfunction "K_2") (pintype "passive"))
      (node (ref "R19") (pin "2") (pinfunction "2_2") (pintype "passive"))
    )
    (net (code "36") (name "Net-(L5-K)") (class "Default")
      (node (ref "L5") (pin "2") (pinfunction "K_2") (pintype "passive"))
      (node (ref "R25") (pin "2") (pinfunction "2_2") (pintype "passive"))
    )
    (net (code "37") (name "Net-(L6-K)") (class "Default")
      (node (ref "L6") (pin "2") (pinfunction "K_2") (pintype "passive"))
      (node (ref "R26") (pin "2") (pinfunction "2_2") (pintype "passive"))
    )
    (net (code "38") (name "Net-(L7-K)") (class "Default")
      (node (ref "L7") (pin "2") (pinfunction "K_2") (pintype "passive"))
      (node (ref "R27") (pin "2") (pinfunction "2_2") (pintype "passive"))
    )
    (net (code "39") (name "Net-(R3-Pad2)") (class "Default")
      (node (ref "R3") (pin "2") (pinfunction "2_2") (pintype "passive"))
      (node (ref "U3") (pin "1") (pinfunction "1_1") (pintype "passive"))
    )
    (net (code "40") (name "Net-(R9-Pad2)") (class "Default")
      (node (ref "R9") (pin "2") (pinfunction "2_2") (pintype "passive"))
      (node (ref "U3") (pin "4") (pinfunction "4_4") (pintype "passive"))
    )
    (net (code "41") (name "Net-(U1-IO14)") (class "Default")
      (node (ref "R6") (pin "1") (pinfunction "1_1") (pintype "passive"))
      (node (ref "U1") (pin "22") (pinfunction "IO14_22") (pintype "bidirectional"))
    )
    (net (code "42") (name "Net-(U2A-BOOT0)") (class "Default")
      (node (ref "R14") (pin "2") (pinfunction "2_2") (pintype "passive"))
      (node (ref "U2") (pin "94") (pinfunction "BOOT0_94") (pintype "input"))
    )
    (net (code "43") (name "Net-(U2A-PB2-BOOT1(PB2))") (class "Default")
      (node (ref "R1") (pin "2") (pinfunction "2_2") (pintype "passive"))
      (node (ref "U2") (pin "37") (pinfunction "PB2-BOOT1(PB2)_37") (pintype "bidirectional"))
    )
    (net (code "44") (name "Net-(U2A-PH0-OSC_IN(PH0))") (class "Default")
      (node (ref "C19") (pin "1") (pinfunction "1_1") (pintype "passive"))
      (node (ref "U2") (pin "12") (pinfunction "PH0-OSC_IN(PH0)_12") (pintype "bidirectional"))
      (node (ref "X1") (pin "3") (pinfunction "3_3") (pintype "passive"))
    )
    (net (code "45") (name "Net-(U2A-PH1-OSC_OUT(PH1))") (class "Default")
      (node (ref "R12") (pin "1") (pinfunction "1_1") (pintype "passive"))
      (node (ref "U2") (pin "13") (pinfunction "PH1-OSC_OUT(PH1)_13") (pintype "bidirectional"))
    )
    (net (code "46") (name "Net-(U2A-VCAP_1)") (class "Default")
      (node (ref "C22") (pin "1") (pinfunction "1_1") (pintype "passive"))
      (node (ref "U2") (pin "49") (pinfunction "VCAP_1_49") (pintype "power_in"))
    )
    (net (code "47") (name "Net-(U2A-VCAP_2)") (class "Default")
      (node (ref "C21") (pin "1") (pinfunction "1_1") (pintype "passive"))
      (node (ref "U2") (pin "73") (pinfunction "VCAP_2_73") (pintype "power_in"))
    )
    (net (code "48") (name "Net-(U4-IN)") (class "Default")
      (node (ref "R11") (pin "1") (pinfunction "1_1") (pintype "passive"))
      (node (ref "U4") (pin "2") (pinfunction "IN_2") (pintype "input"))
    )
    (net (code "49") (name "Net-(U4-INH)") (class "Default")
      (node (ref "R13") (pin "1") (pinfunction "1_1") (pintype "passive"))
      (node (ref "U4") (pin "3") (pinfunction "INH_3") (pintype "input"))
    )
    (net (code "50") (name "Net-(U4-IS)") (class "Default")
      (node (ref "R16") (pin "1") (pinfunction "1_1") (pintype "passive"))
      (node (ref "U4") (pin "6") (pinfunction "IS_6") (pintype "output"))
    )
    (net (code "51") (name "Net-(U4-SR)") (class "Default")
      (node (ref "R15") (pin "1") (pinfunction "1_1") (pintype "passive"))
      (node (ref "U4") (pin "5") (pinfunction "SR_5") (pintype "input"))
    )
    (net (code "52") (name "Net-(U5-IN)") (class "Default")
      (node (ref "R20") (pin "1") (pinfunction "1_1") (pintype "passive"))
      (node (ref "U5") (pin "2") (pinfunction "IN_2") (pintype "input"))
    )
    (net (code "53") (name "Net-(U5-INH)") (class "Default")
      (node (ref "R21") (pin "1") (pinfunction "1_1") (pintype "passive"))
      (node (ref "U5") (pin "3") (pinfunction "INH_3") (pintype "input"))
    )
    (net (code "54") (name "Net-(U5-IS)") (class "Default")
      (node (ref "R23") (pin "1") (pinfunction "1_1") (pintype "passive"))
      (node (ref "U5") (pin "6") (pinfunction "IS_6") (pintype "output"))
    )
    (net (code "55") (name "Net-(U5-SR)") (class "Default")
      (node (ref "R22") (pin "1") (pinfunction "1_1") (pintype "passive"))
      (node (ref "U5") (pin "5") (pinfunction "SR_5") (pintype "input"))
    )
    (net (code "56") (name "unconnected-(U1-IO1-Pad39)") (class "Default")
      (node (ref "U1") (pin "39") (pinfunction "IO1_39") (pintype "bidirectional+no_connect"))
    )
    (net (code "57") (name "unconnected-(U1-IO2-Pad38)") (class "Default")
      (node (ref "U1") (pin "38") (pinfunction "IO2_38") (pintype "bidirectional+no_connect"))
    )
    (net (code "58") (name "unconnected-(U1-IO3-Pad15)") (class "Default")
      (node (ref "U1") (pin "15") (pinfunction "IO3_15") (pintype "bidirectional+no_connect"))
    )
    (net (code "59") (name "unconnected-(U1-IO4-Pad4)") (class "Default")
      (node (ref "U1") (pin "4") (pinfunction "IO4_4") (pintype "bidirectional+no_connect"))
    )
    (net (code "60") (name "unconnected-(U1-IO5-Pad5)") (class "Default")
      (node (ref "U1") (pin "5") (pinfunction "IO5_5") (pintype "bidirectional+no_connect"))
    )
    (net (code "61") (name "unconnected-(U1-IO6-Pad6)") (class "Default")
      (node (ref "U1") (pin "6") (pinfunction "IO6_6") (pintype "bidirectional+no_connect"))
    )
    (net (code "62") (name "unconnected-(U1-IO7-Pad7)") (class "Default")
      (node (ref "U1") (pin "7") (pinfunction "IO7_7") (pintype "bidirectional+no_connect"))
    )
    (net (code "63") (name "unconnected-(U1-IO8-Pad12)") (class "Default")
      (node (ref "U1") (pin "12") (pinfunction "IO8_12") (pintype "bidirectional+no_connect"))
    )
    (net (code "64") (name "unconnected-(U1-IO9-Pad17)") (class "Default")
      (node (ref "U1") (pin "17") (pinfunction "IO9_17") (pintype "bidirectional+no_connect"))
    )
    (net (code "65") (name "unconnected-(U1-IO10-Pad18)") (class "Default")
      (node (ref "U1") (pin "18") (pinfunction "IO10_18") (pintype "bidirectional+no_connect"))
    )
    (net (code "66") (name "unconnected-(U1-IO11-Pad19)") (class "Default")
      (node (ref "U1") (pin "19") (pinfunction "IO11_19") (pintype "bidirectional+no_connect"))
    )
    (net (code "67") (name "unconnected-(U1-IO12-Pad20)") (class "Default")
      (node (ref "U1") (pin "20") (pinfunction "IO12_20") (pintype "bidirectional+no_connect"))
    )
    (net (code "68") (name "unconnected-(U1-IO13-Pad21)") (class "Default")
      (node (ref "U1") (pin "21") (pinfunction "IO13_21") (pintype "bidirectional+no_connect"))
    )
    (net (code "69") (name "unconnected-(U1-IO15-Pad8)") (class "Default")
      (node (ref "U1") (pin "8") (pinfunction "IO15_8") (pintype "bidirectional+no_connect"))
    )
    (net (code "70") (name "unconnected-(U1-IO16-Pad9)") (class "Default")
      (node (ref "U1") (pin "9") (pinfunction "IO16_9") (pintype "bidirectional+no_connect"))
    )
    (net (code "71") (name "unconnected-(U1-IO19-Pad13)") (class "Default")
      (node (ref "U1") (pin "13") (pinfunction "IO19_13") (pintype "bidirectional+no_connect"))
    )
    (net (code "72") (name "unconnected-(U1-IO20-Pad14)") (class "Default")
      (node (ref "U1") (pin "14") (pinfunction "IO20_14") (pintype "bidirectional+no_connect"))
    )
    (net (code "73") (name "unconnected-(U1-IO21-Pad23)") (class "Default")
      (node (ref "U1") (pin "23") (pinfunction "IO21_23") (pintype "bidirectional+no_connect"))
    )
    (net (code "74") (name "unconnected-(U1-IO35-Pad28)") (class "Default")
      (node (ref "U1") (pin "28") (pinfunction "IO35_28") (pintype "bidirectional+no_connect"))
    )
    (net (code "75") (name "unconnected-(U1-IO36-Pad29)") (class "Default")
      (node (ref "U1") (pin "29") (pinfunction "IO36_29") (pintype "bidirectional+no_connect"))
    )
    (net (code "76") (name "unconnected-(U1-IO37-Pad30)") (class "Default")
      (node (ref "U1") (pin "30") (pinfunction "IO37_30") (pintype "bidirectional+no_connect"))
    )
    (net (code "77") (name "unconnected-(U1-IO38-Pad31)") (class "Default")
      (node (ref "U1") (pin "31") (pinfunction "IO38_31") (pintype "bidirectional+no_connect"))
    )
    (net (code "78") (name "unconnected-(U1-IO39-Pad32)") (class "Default")
      (node (ref "U1") (pin "32") (pinfunction "IO39_32") (pintype "bidirectional+no_connect"))
    )
    (net (code "79") (name "unconnected-(U1-IO40-Pad33)") (class "Default")
      (node (ref "U1") (pin "33") (pinfunction "IO40_33") (pintype "bidirectional+no_connect"))
    )
    (net (code "80") (name "unconnected-(U1-IO41-Pad34)") (class "Default")
      (node (ref "U1") (pin "34") (pinfunction "IO41_34") (pintype "bidirectional+no_connect"))
    )
    (net (code "81") (name "unconnected-(U1-IO42-Pad35)") (class "Default")
      (node (ref "U1") (pin "35") (pinfunction "IO42_35") (pintype "bidirectional+no_connect"))
    )
    (net (code "82") (name "unconnected-(U1-IO45-Pad26)") (class "Default")
      (node (ref "U1") (pin "26") (pinfunction "IO45_26") (pintype "bidirectional+no_connect"))
    )
    (net (code "83") (name "unconnected-(U1-IO46-Pad16)") (class "Default")
      (node (ref "U1") (pin "16") (pinfunction "IO46_16") (pintype "bidirectional+no_connect"))
    )
    (net (code "84") (name "unconnected-(U1-IO47-Pad24)") (class "Default")
      (node (ref "U1") (pin "24") (pinfunction "IO47_24") (pintype "bidirectional+no_connect"))
    )
    (net (code "85") (name "unconnected-(U1-IO48-Pad25)") (class "Default")
      (node (ref "U1") (pin "25") (pinfunction "IO48_25") (pintype "bidirectional+no_connect"))
    )
    (net (code "86") (name "unconnected-(U2A-PA0-WKUP(PA0)-Pad23)") (class "Default")
      (node (ref "U2") (pin "23") (pinfunction "PA0-WKUP(PA0)_23") (pintype "bidirectional+no_connect"))
    )
    (net (code "87") (name "unconnected-(U2A-PA1-Pad24)") (class "Default")
      (node (ref "U2") (pin "24") (pinfunction "PA1_24") (pintype "bidirectional+no_connect"))
    )
    (net (code "88") (name "unconnected-(U2A-PA4-Pad29)") (class "Default")
      (node (ref "U2") (pin "29") (pinfunction "PA4_29") (pintype "bidirectional+no_connect"))
    )
    (net (code "89") (name "unconnected-(U2A-PA5-Pad30)") (class "Default")
      (node (ref "U2") (pin "30") (pinfunction "PA5_30") (pintype "bidirectional+no_connect"))
    )
    (net (code "90") (name "unconnected-(U2A-PA6-Pad31)") (class "Default")
      (node (ref "U2") (pin "31") (pinfunction "PA6_31") (pintype "bidirectional+no_connect"))
    )
    (net (code "91") (name "unconnected-(U2A-PA7-Pad32)") (class "Default")
      (node (ref "U2") (pin "32") (pinfunction "PA7_32") (pintype "bidirectional+no_connect"))
    )
    (net (code "92") (name "unconnected-(U2A-PA11-Pad70)") (class "Default")
      (node (ref "U2") (pin "70") (pinfunction "PA11_70") (pintype "bidirectional+no_connect"))
    )
    (net (code "93") (name "unconnected-(U2A-PA12-Pad71)") (class "Default")
      (node (ref "U2") (pin "71") (pinfunction "PA12_71") (pintype "bidirectional+no_connect"))
    )
    (net (code "94") (name "unconnected-(U2A-PA15(JTDI)-Pad77)") (class "Default")
      (node (ref "U2") (pin "77") (pinfunction "PA15(JTDI)_77") (pintype "bidirectional+no_connect"))
    )
    (net (code "95") (name "unconnected-(U2A-PB0-Pad35)") (class "Default")
      (node (ref "U2") (pin "35") (pinfunction "PB0_35") (pintype "bidirectional+no_connect"))
    )
    (net (code "96") (name "unconnected-(U2A-PB1-Pad36)") (class "Default")
      (node (ref "U2") (pin "36") (pinfunction "PB1_36") (pintype "bidirectional+no_connect"))
    )
    (net (code "97") (name "unconnected-(U2A-PB3(JTDO{slash}TRACESWO)-Pad89)") (class "Default")
      (node (ref "U2") (pin "89") (pinfunction "PB3(JTDO/TRACESWO)_89") (pintype "bidirectional+no_connect"))
    )
    (net (code "98") (name "unconnected-(U2A-PB4(NJTRST)-Pad90)") (class "Default")
      (node (ref "U2") (pin "90") (pinfunction "PB4(NJTRST)_90") (pintype "bidirectional+no_connect"))
    )
    (net (code "99") (name "unconnected-(U2A-PB7-Pad93)") (class "Default")
      (node (ref "U2") (pin "93") (pinfunction "PB7_93") (pintype "bidirectional+no_connect"))
    )
    (net (code "100") (name "unconnected-(U2A-PB10-Pad47)") (class "Default")
      (node (ref "U2") (pin "47") (pinfunction "PB10_47") (pintype "bidirectional+no_connect"))
    )
    (net (code "101") (name "unconnected-(U2A-PB11-Pad48)") (class "Default")
      (node (ref "U2") (pin "48") (pinfunction "PB11_48") (pintype "bidirectional+no_connect"))
    )
    (net (code "102") (name "unconnected-(U2A-PB12-Pad51)") (class "Default")
      (node (ref "U2") (pin "51") (pinfunction "PB12_51") (pintype "bidirectional+no_connect"))
    )
    (net (code "103") (name "unconnected-(U2A-PB13-Pad52)") (class "Default")
      (node (ref "U2") (pin "52") (pinfunction "PB13_52") (pintype "bidirectional+no_connect"))
    )
    (net (code "104") (name "unconnected-(U2A-PB14-Pad53)") (class "Default")
      (node (ref "U2") (pin "53") (pinfunction "PB14_53") (pintype "bidirectional+no_connect"))
    )
    (net (code "105") (name "unconnected-(U2A-PB15-Pad54)") (class "Default")
      (node (ref "U2") (pin "54") (pinfunction "PB15_54") (pintype "bidirectional+no_connect"))
    )
    (net (code "106") (name "unconnected-(U2A-PC0-Pad15)") (class "Default")
      (node (ref "U2") (pin "15") (pinfunction "PC0_15") (pintype "bidirectional+no_connect"))
    )
    (net (code "107") (name "unconnected-(U2A-PC1-Pad16)") (class "Default")
      (node (ref "U2") (pin "16") (pinfunction "PC1_16") (pintype "bidirectional+no_connect"))
    )
    (net (code "108") (name "unconnected-(U2A-PC2-Pad17)") (class "Default")
      (node (ref "U2") (pin "17") (pinfunction "PC2_17") (pintype "bidirectional+no_connect"))
    )
    (net (code "109") (name "unconnected-(U2A-PC3-Pad18)") (class "Default")
      (node (ref "U2") (pin "18") (pinfunction "PC3_18") (pintype "bidirectional+no_connect"))
    )
    (net (code "110") (name "unconnected-(U2A-PC4-Pad33)") (class "Default")
      (node (ref "U2") (pin "33") (pinfunction "PC4_33") (pintype "bidirectional+no_connect"))
    )
    (net (code "111") (name "unconnected-(U2A-PC5-Pad34)") (class "Default")
      (node (ref "U2") (pin "34") (pinfunction "PC5_34") (pintype "bidirectional+no_connect"))
    )
    (net (code "112") (name "unconnected-(U2A-PC6-Pad63)") (class "Default")
      (node (ref "U2") (pin "63") (pinfunction "PC6_63") (pintype "bidirectional+no_connect"))
    )
    (net (code "113") (name "unconnected-(U2A-PC7-Pad64)") (class "Default")
      (node (ref "U2") (pin "64") (pinfunction "PC7_64") (pintype "bidirectional+no_connect"))
    )
    (net (code "114") (name "unconnected-(U2A-PC8-Pad65)") (class "Default")
      (node (ref "U2") (pin "65") (pinfunction "PC8_65") (pintype "bidirectional+no_connect"))
    )
    (net (code "115") (name "unconnected-(U2A-PC10-Pad78)") (class "Default")
      (node (ref "U2") (pin "78") (pinfunction "PC10_78") (pintype "bidirectional+no_connect"))
    )
    (net (code "116") (name "unconnected-(U2A-PC11-Pad79)") (class "Default")
      (node (ref "U2") (pin "79") (pinfunction "PC11_79") (pintype "bidirectional+no_connect"))
    )
    (net (code "117") (name "unconnected-(U2A-PC12-Pad80)") (class "Default")
      (node (ref "U2") (pin "80") (pinfunction "PC12_80") (pintype "bidirectional+no_connect"))
    )
    (net (code "118") (name "unconnected-(U2A-PC13-Pad7)") (class "Default")
      (node (ref "U2") (pin "7") (pinfunction "PC13_7") (pintype "bidirectional+no_connect"))
    )
    (net (code "119") (name "unconnected-(U2A-PC14-OSC32_IN(PC14)-Pad8)") (class "Default")
      (node (ref "U2") (pin "8") (pinfunction "PC14-OSC32_IN(PC14)_8") (pintype "bidirectional+no_connect"))
    )
    (net (code "120") (name "unconnected-(U2A-PC15-OSC32_OUT(PC15)-Pad9)") (class "Default")
      (node (ref "U2") (pin "9") (pinfunction "PC15-OSC32_OUT(PC15)_9") (pintype "bidirectional+no_connect"))
    )
    (net (code "121") (name "unconnected-(U2A-PD0-Pad81)") (class "Default")
      (node (ref "U2") (pin "81") (pinfunction "PD0_81") (pintype "bidirectional+no_connect"))
    )
    (net (code "122") (name "unconnected-(U2A-PD1-Pad82)") (class "Default")
      (node (ref "U2") (pin "82") (pinfunction "PD1_82") (pintype "bidirectional+no_connect"))
    )
    (net (code "123") (name "unconnected-(U2A-PD2-Pad83)") (class "Default")
      (node (ref "U2") (pin "83") (pinfunction "PD2_83") (pintype "bidirectional+no_connect"))
    )
    (net (code "124") (name "unconnected-(U2A-PD3-Pad84)") (class "Default")
      (node (ref "U2") (pin "84") (pinfunction "PD3_84") (pintype "bidirectional+no_connect"))
    )
    (net (code "125") (name "unconnected-(U2A-PD4-Pad85)") (class "Default")
      (node (ref "U2") (pin "85") (pinfunction "PD4_85") (pintype "bidirectional+no_connect"))
    )
    (net (code "126") (name "unconnected-(U2A-PD5-Pad86)") (class "Default")
      (node (ref "U2") (pin "86") (pinfunction "PD5_86") (pintype "bidirectional+no_connect"))
    )
    (net (code "127") (name "unconnected-(U2A-PD6-Pad87)") (class "Default")
      (node (ref "U2") (pin "87") (pinfunction "PD6_87") (pintype "bidirectional+no_connect"))
    )
    (net (code "128") (name "unconnected-(U2A-PD7-Pad88)") (class "Default")
      (node (ref "U2") (pin "88") (pinfunction "PD7_88") (pintype "bidirectional+no_connect"))
    )
    (net (code "129") (name "unconnected-(U2A-PD8-Pad55)") (class "Default")
      (node (ref "U2") (pin "55") (pinfunction "PD8_55") (pintype "bidirectional+no_connect"))
    )
    (net (code "130") (name "unconnected-(U2A-PD9-Pad56)") (class "Default")
      (node (ref "U2") (pin "56") (pinfunction "PD9_56") (pintype "bidirectional+no_connect"))
    )
    (net (code "131") (name "unconnected-(U2A-PD10-Pad57)") (class "Default")
      (node (ref "U2") (pin "57") (pinfunction "PD10_57") (pintype "bidirectional+no_connect"))
    )
    (net (code "132") (name "unconnected-(U2A-PD11-Pad58)") (class "Default")
      (node (ref "U2") (pin "58") (pinfunction "PD11_58") (pintype "bidirectional+no_connect"))
    )
    (net (code "133") (name "unconnected-(U2A-PD12-Pad59)") (class "Default")
      (node (ref "U2") (pin "59") (pinfunction "PD12_59") (pintype "bidirectional+no_connect"))
    )
    (net (code "134") (name "unconnected-(U2A-PD13-Pad60)") (class "Default")
      (node (ref "U2") (pin "60") (pinfunction "PD13_60") (pintype "bidirectional+no_connect"))
    )
    (net (code "135") (name "unconnected-(U2A-PD14-Pad61)") (class "Default")
      (node (ref "U2") (pin "61") (pinfunction "PD14_61") (pintype "bidirectional+no_connect"))
    )
    (net (code "136") (name "unconnected-(U2A-PD15-Pad62)") (class "Default")
      (node (ref "U2") (pin "62") (pinfunction "PD15_62") (pintype "bidirectional+no_connect"))
    )
    (net (code "137") (name "unconnected-(U2A-PE0-Pad97)") (class "Default")
      (node (ref "U2") (pin "97") (pinfunction "PE0_97") (pintype "bidirectional+no_connect"))
    )
    (net (code "138") (name "unconnected-(U2A-PE1-Pad98)") (class "Default")
      (node (ref "U2") (pin "98") (pinfunction "PE1_98") (pintype "bidirectional+no_connect"))
    )
    (net (code "139") (name "unconnected-(U2A-PE5-Pad4)") (class "Default")
      (node (ref "U2") (pin "4") (pinfunction "PE5_4") (pintype "bidirectional+no_connect"))
    )
    (net (code "140") (name "unconnected-(U2A-PE6-Pad5)") (class "Default")
      (node (ref "U2") (pin "5") (pinfunction "PE6_5") (pintype "bidirectional+no_connect"))
    )
    (net (code "141") (name "unconnected-(U2A-PE7-Pad38)") (class "Default")
      (node (ref "U2") (pin "38") (pinfunction "PE7_38") (pintype "bidirectional+no_connect"))
    )
    (net (code "142") (name "unconnected-(U2A-PE8-Pad39)") (class "Default")
      (node (ref "U2") (pin "39") (pinfunction "PE8_39") (pintype "bidirectional+no_connect"))
    )
    (net (code "143") (name "unconnected-(U2A-PE9-Pad40)") (class "Default")
      (node (ref "U2") (pin "40") (pinfunction "PE9_40") (pintype "bidirectional+no_connect"))
    )
    (net (code "144") (name "unconnected-(U2A-PE10-Pad41)") (class "Default")
      (node (ref "U2") (pin "41") (pinfunction "PE10_41") (pintype "bidirectional+no_connect"))
    )
    (net (code "145") (name "unconnected-(U2A-PE11-Pad42)") (class "Default")
      (node (ref "U2") (pin "42") (pinfunction "PE11_42") (pintype "bidirectional+no_connect"))
    )
    (net (code "146") (name "unconnected-(U2A-PE12-Pad43)") (class "Default")
      (node (ref "U2") (pin "43") (pinfunction "PE12_43") (pintype "bidirectional+no_connect"))
    )
    (net (code "147") (name "unconnected-(U2A-PE13-Pad44)") (class "Default")
      (node (ref "U2") (pin "44") (pinfunction "PE13_44") (pintype "bidirectional+no_connect"))
    )
    (net (code "148") (name "unconnected-(U2A-PE14-Pad45)") (class "Default")
      (node (ref "U2") (pin "45") (pinfunction "PE14_45") (pintype "bidirectional+no_connect"))
    )
    (net (code "149") (name "unconnected-(U2A-PE15-Pad46)") (class "Default")
      (node (ref "U2") (pin "46") (pinfunction "PE15_46") (pintype "bidirectional+no_connect"))
    )
  )
)
